# S7G2_Titan_Teknic_motor_sim.net
KiCad netlist of a schematic drawn in EAGLE
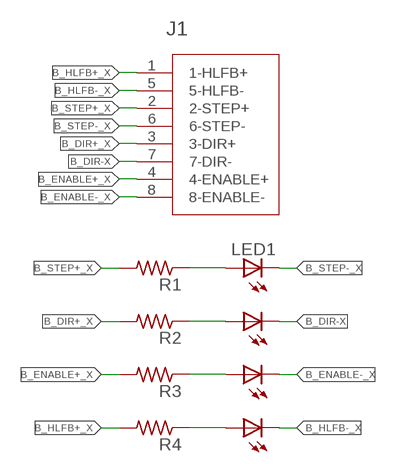
[diagram p0: schematic, sheet 1]

(export (version "E")
  (design (tool "Eeschema 10.0.6"))
  (components
    (comp (ref "J1")
      (value "TEKNIC_MOTOR_SD_8PIN")
      (footprint "eagle-import:CON_39281083")
      (fields
        (field (name "MANUFACTURER_PART_NUMBER") "39281083")
        (field (name "COPYRIGHT") "Copyright (C) 2022 Ultra Librarian. All rights reserved.")
      )
      (libsource (lib "eagle-import") (part "TEKNIC_MOTOR_SD_8PIN"))
    )
    (comp (ref "LED1")
      (value "Green")
      (footprint "eagle-import:0805")
      (fields (field (name "PARTNO") "LG R971-KN-1"))
      (libsource (lib "eagle-import") (part "LED_0805_GREEN"))
    )
    (comp (ref "LED2")
      (value "Green")
      (footprint "eagle-import:0805")
      (fields (field (name "PARTNO") "LG R971-KN-1"))
      (libsource (lib "eagle-import") (part "LED_0805_GREEN"))
    )
    (comp (ref "LED3")
      (value "Green")
      (footprint "eagle-import:0805")
      (fields (field (name "PARTNO") "LG R971-KN-1"))
      (libsource (lib "eagle-import") (part "LED_0805_GREEN"))
    )
    (comp (ref "LED4")
      (value "Green")
      (footprint "eagle-import:0805")
      (fields (field (name "PARTNO") "LG R971-KN-1"))
      (libsource (lib "eagle-import") (part "LED_0805_GREEN"))
    )
    (comp (ref "R1")
      (value "R_0805")
      (footprint "eagle-import:0805")
      (libsource (lib "eagle-import") (part "R_0805"))
    )
    (comp (ref "R2")
      (value "R_0805")
      (footprint "eagle-import:0805")
      (libsource (lib "eagle-import") (part "R_0805"))
    )
    (comp (ref "R3")
      (value "R_0805")
      (footprint "eagle-import:0805")
      (libsource (lib "eagle-import") (part "R_0805"))
    )
    (comp (ref "R4")
      (value "R_0805")
      (footprint "eagle-import:0805")
      (libsource (lib "eagle-import") (part "R_0805"))
    )
  )
  (nets
    (net (code "1") (name "B_DIR+_X") (class "Default")
      (node (ref "J1") (pin "3") (pinfunction "3-DIR+_3") (pintype "passive"))
      (node (ref "R2") (pin "2") (pinfunction "2_2") (pintype "passive"))
    )
    (net (code "2") (name "B_DIR-X") (class "Default")
      (node (ref "J1") (pin "7") (pinfunction "7-DIR-_7") (pintype "passive"))
      (node (ref "LED2") (pin "2") (pinfunction "C_2") (pintype "passive"))
    )
    (net (code "3") (name "B_ENABLE+_X") (class "Default")
      (node (ref "J1") (pin "4") (pinfunction "4-ENABLE+_4") (pintype "passive"))
      (node (ref "R3") (pin "2") (pinfunction "2_2") (pintype "passive"))
    )
    (net (code "4") (name "B_ENABLE-_X") (class "Default")
      (node (ref "J1") (pin "8") (pinfunction "8-ENABLE-_8") (pintype "passive"))
      (node (ref "LED3") (pin "2") (pinfunction "C_2") (pintype "passive"))
    )
    (net (code "5") (name "B_HLFB+_X") (class "Default")
      (node (ref "J1") (pin "1") (pinfunction "1-HLFB+_1") (pintype "passive"))
      (node (ref "R4") (pin "2") (pinfunction "2_2") (pintype "passive"))
    )
    (net (code "6") (name "B_HLFB-_X") (class "Default")
      (node (ref "J1") (pin "5") (pinfunction "5-HLFB-_5") (pintype "passive"))
      (node (ref "LED4") (pin "2") (pinfunction "C_2") (pintype "passive"))
    )
    (net (code "7") (name "B_STEP+_X") (class "Default")
      (node (ref "J1") (pin "2") (pinfunction "2-STEP+_2") (pintype "passive"))
      (node (ref "R1") (pin "2") (pinfunction "2_2") (pintype "passive"))
    )
    (net (code "8") (name "B_STEP-_X") (class "Default")
      (node (ref "J1") (pin "6") (pinfunction "6-STEP-_6") (pintype "passive"))
      (node (ref "LED1") (pin "2") (pinfunction "C_2") (pintype "passive"))
    )
    (net (code "9") (name "Net-(LED1-A)") (class "Default")
      (node (ref "LED1") (pin "1") (pinfunction "A_1") (pintype "passive"))
      (node (ref "R1") (pin "1") (pinfunction "1_1") (pintype "passive"))
    )
    (net (code "10") (name "Net-(LED2-A)") (class "Default")
      (node (ref "LED2") (pin "1") (pinfunction "A_1") (pintype "passive"))
      (node (ref "R2") (pin "1") (pinfunction "1_1") (pintype "passive"))
    )
    (net (code "11") (name "Net-(LED3-A)") (class "Default")
      (node (ref "LED3") (pin "1") (pinfunction "A_1") (pintype "passive"))
      (node (ref "R3") (pin "1") (pinfunction "1_1") (pintype "passive"))
    )
    (net (code "12") (name "Net-(LED4-A)") (class "Default")
      (node (ref "LED4") (pin "1") (pinfunction "A_1") (pintype "passive"))
      (node (ref "R4") (pin "1") (pinfunction "1_1") (pintype "passive"))
    )
  )
)
